# TSAL_3_5_16.net
KiCad netlist of a schematic drawn in EAGLE
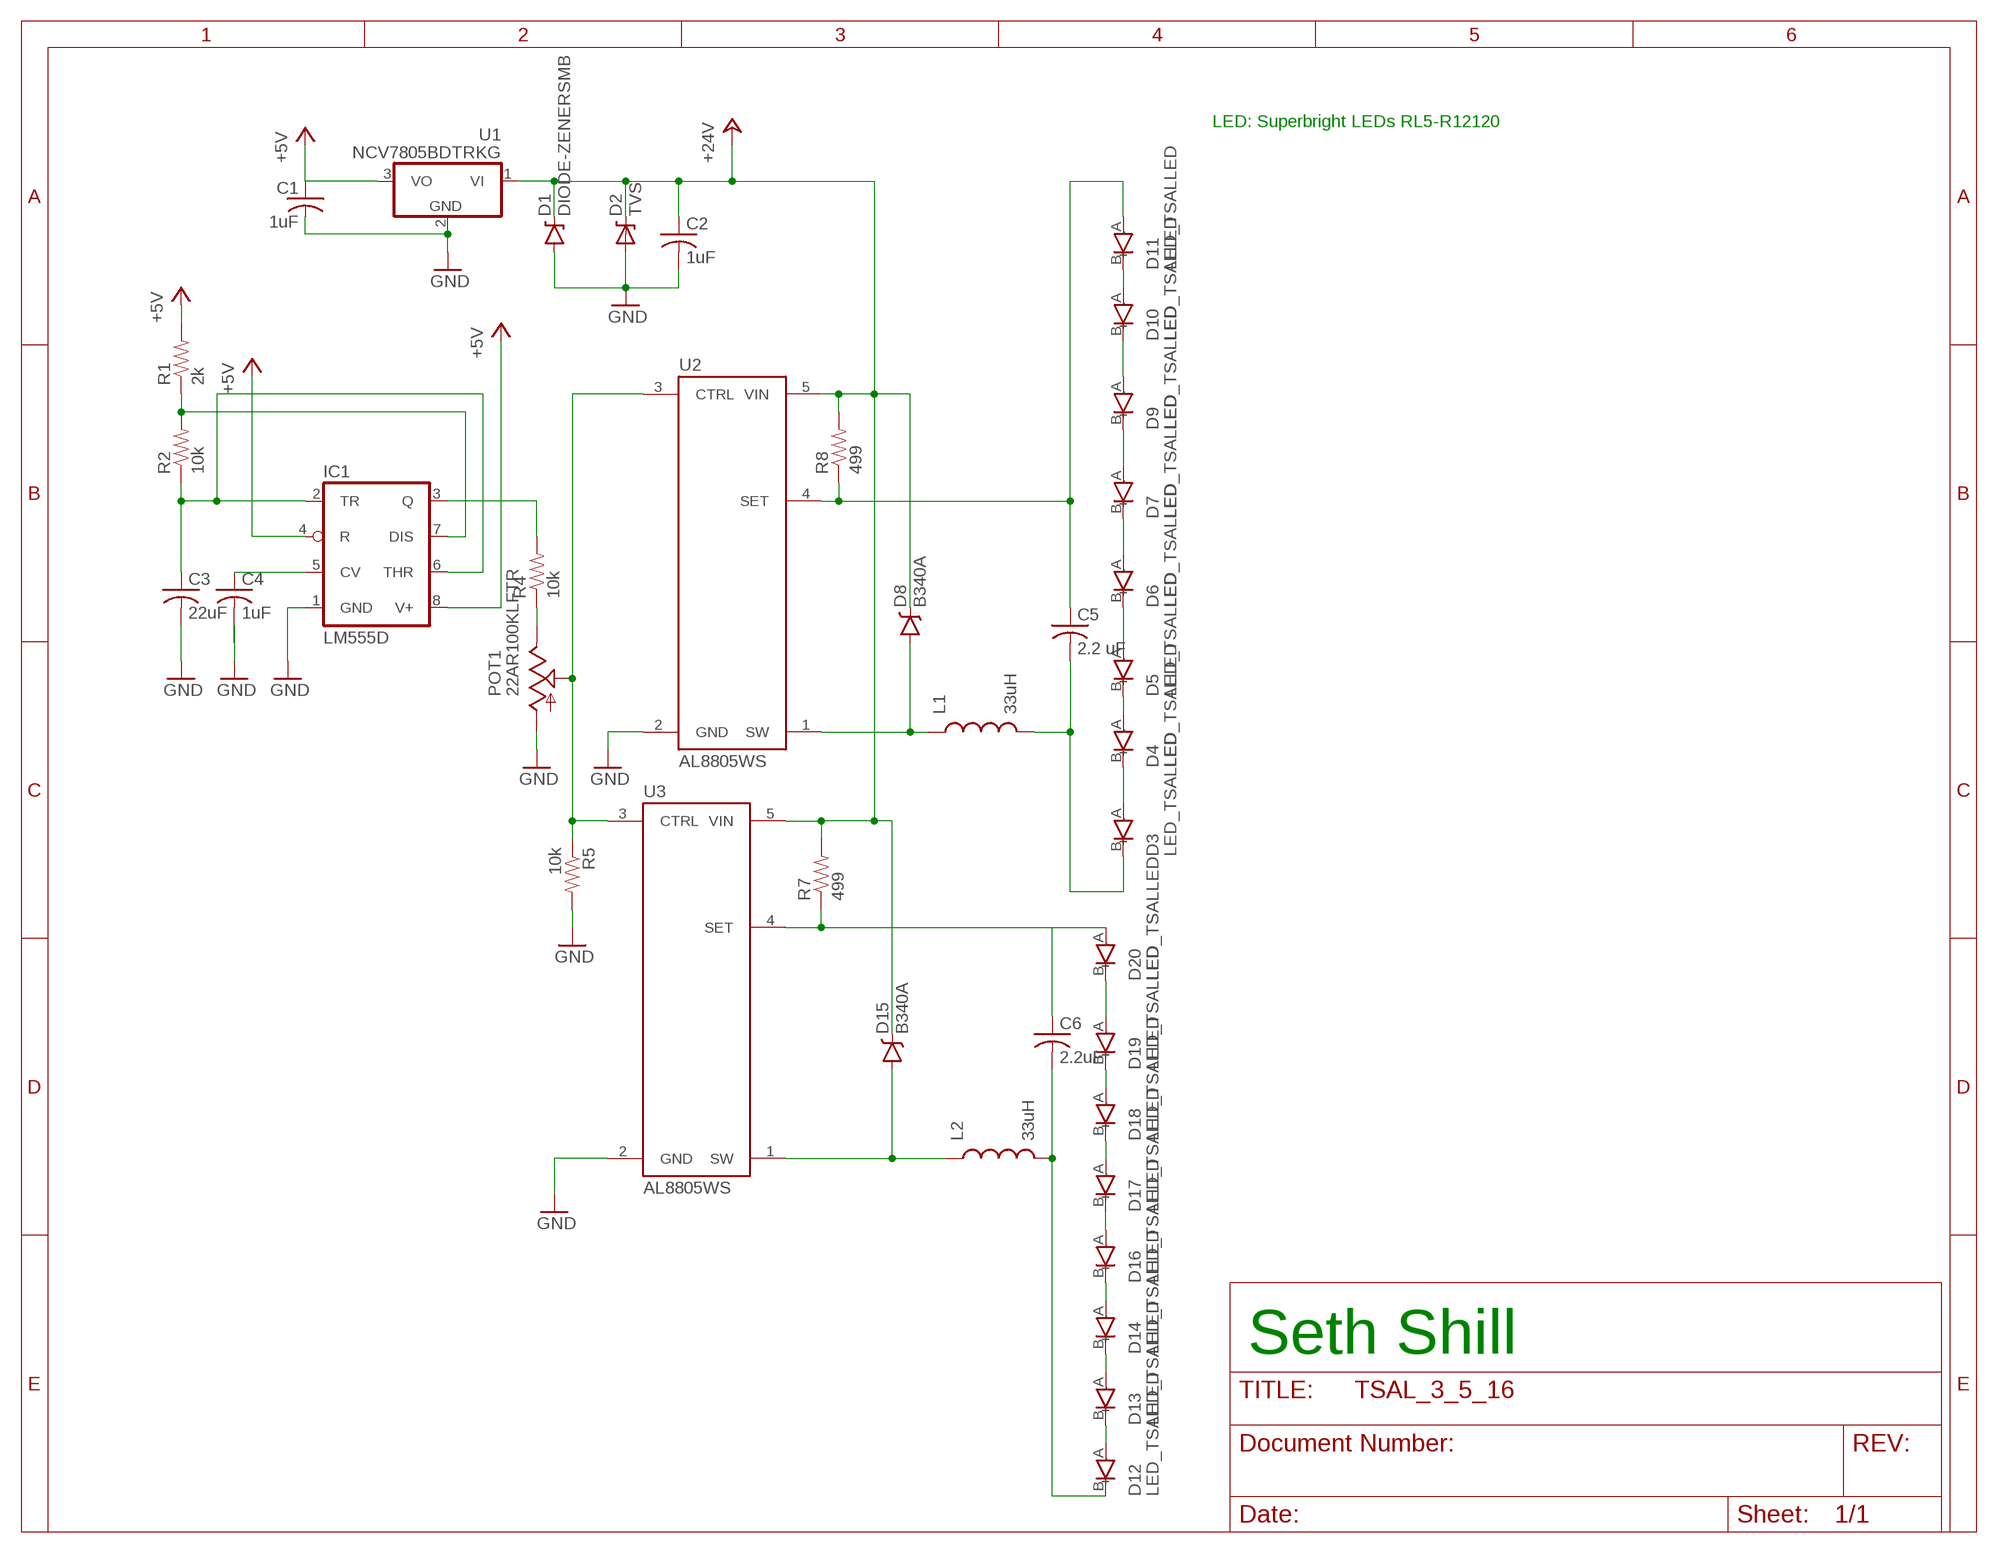
[diagram p0: schematic, sheet 1]

(export (version "E")
  (design (tool "Eeschema 10.0.6"))
  (components
    (comp (ref "C1")
      (value "1uF")
      (footprint "eagle-import:0805@1")
      (fields (field (name "PARTNO") "UMK212F105ZG-T"))
      (libsource (lib "eagle-import") (part "CAP_1UF_50V_0805"))
    )
    (comp (ref "C2")
      (value "1uF")
      (footprint "eagle-import:0805@1")
      (fields (field (name "PARTNO") "UMK212F105ZG-T"))
      (libsource (lib "eagle-import") (part "CAP_1UF_50V_0805"))
    )
    (comp (ref "C3")
      (value "22uF")
      (footprint "eagle-import:0805@1")
      (fields (field (name "PARTNO") "CL21A226MQCLQNC"))
      (libsource (lib "eagle-import") (part "CAP_22UF_6.3V_0805"))
    )
    (comp (ref "C4")
      (value "1uF")
      (footprint "eagle-import:0805@1")
      (fields (field (name "PARTNO") "UMK212F105ZG-T"))
      (libsource (lib "eagle-import") (part "CAP_1UF_50V_0805"))
    )
    (comp (ref "C5")
      (value "2.2 uF")
      (footprint "eagle-import:0603@1")
      (fields (field (name "PARTNO") "EMK107F225ZA-T"))
      (libsource (lib "eagle-import") (part "CAP_2.2UF_16V_0603"))
    )
    (comp (ref "C6")
      (value "2.2uF")
      (footprint "eagle-import:0603@1")
      (fields (field (name "PARTNO") "EMK107F225ZA-T"))
      (libsource (lib "eagle-import") (part "CAP_2.2UF_16V_0603"))
    )
    (comp (ref "D1")
      (value "DIODE-ZENERSMB")
      (footprint "eagle-import:SMB-DIODE")
      (libsource (lib "eagle-import") (part "DIODE-ZENERSMB"))
    )
    (comp (ref "D2")
      (value "TVS")
      (footprint "eagle-import:DO-214AC")
      (libsource (lib "eagle-import") (part "TVS"))
    )
    (comp (ref "D3")
      (value "LED_TSALLED")
      (footprint "eagle-import:LED_TSAL")
      (libsource (lib "eagle-import") (part "LED_TSALLED"))
    )
    (comp (ref "D4")
      (value "LED_TSALLED")
      (footprint "eagle-import:LED_TSAL")
      (libsource (lib "eagle-import") (part "LED_TSALLED"))
    )
    (comp (ref "D5")
      (value "LED_TSALLED")
      (footprint "eagle-import:LED_TSAL")
      (libsource (lib "eagle-import") (part "LED_TSALLED"))
    )
    (comp (ref "D6")
      (value "LED_TSALLED")
      (footprint "eagle-import:LED_TSAL")
      (libsource (lib "eagle-import") (part "LED_TSALLED"))
    )
    (comp (ref "D7")
      (value "LED_TSALLED")
      (footprint "eagle-import:LED_TSAL")
      (libsource (lib "eagle-import") (part "LED_TSALLED"))
    )
    (comp (ref "D8")
      (value "B340A")
      (footprint "eagle-import:SMA-DIODE")
      (libsource (lib "eagle-import") (part "DIODE-SCHOTTKY-B340A"))
    )
    (comp (ref "D9")
      (value "LED_TSALLED")
      (footprint "eagle-import:LED_TSAL")
      (libsource (lib "eagle-import") (part "LED_TSALLED"))
    )
    (comp (ref "D10")
      (value "LED_TSALLED")
      (footprint "eagle-import:LED_TSAL")
      (libsource (lib "eagle-import") (part "LED_TSALLED"))
    )
    (comp (ref "D11")
      (value "LED_TSALLED")
      (footprint "eagle-import:LED_TSAL")
      (libsource (lib "eagle-import") (part "LED_TSALLED"))
    )
    (comp (ref "D12")
      (value "LED_TSALLED")
      (footprint "eagle-import:LED_TSAL")
      (libsource (lib "eagle-import") (part "LED_TSALLED"))
    )
    (comp (ref "D13")
      (value "LED_TSALLED")
      (footprint "eagle-import:LED_TSAL")
      (libsource (lib "eagle-import") (part "LED_TSALLED"))
    )
    (comp (ref "D14")
      (value "LED_TSALLED")
      (footprint "eagle-import:LED_TSAL")
      (libsource (lib "eagle-import") (part "LED_TSALLED"))
    )
    (comp (ref "D15")
      (value "B340A")
      (footprint "eagle-import:SMA-DIODE")
      (libsource (lib "eagle-import") (part "DIODE-SCHOTTKY-B340A"))
    )
    (comp (ref "D16")
      (value "LED_TSALLED")
      (footprint "eagle-import:LED_TSAL")
      (libsource (lib "eagle-import") (part "LED_TSALLED"))
    )
    (comp (ref "D17")
      (value "LED_TSALLED")
      (footprint "eagle-import:LED_TSAL")
      (libsource (lib "eagle-import") (part "LED_TSALLED"))
    )
    (comp (ref "D18")
      (value "LED_TSALLED")
      (footprint "eagle-import:LED_TSAL")
      (libsource (lib "eagle-import") (part "LED_TSALLED"))
    )
    (comp (ref "D19")
      (value "LED_TSALLED")
      (footprint "eagle-import:LED_TSAL")
      (libsource (lib "eagle-import") (part "LED_TSALLED"))
    )
    (comp (ref "D20")
      (value "LED_TSALLED")
      (footprint "eagle-import:LED_TSAL")
      (libsource (lib "eagle-import") (part "LED_TSALLED"))
    )
    (comp (ref "IC1")
      (value "LM555D")
      (footprint "eagle-import:SO08")
      (libsource (lib "eagle-import") (part "555DLM"))
    )
    (comp (ref "L1")
      (value "33uH")
      (footprint "eagle-import:1007")
      (fields (field (name "PARTNO") "CB2518T330K"))
      (libsource (lib "eagle-import") (part "INDUCTOR1007"))
    )
    (comp (ref "L2")
      (value "33uH")
      (footprint "eagle-import:1007")
      (fields (field (name "PARTNO") "CB2518T330K"))
      (libsource (lib "eagle-import") (part "INDUCTOR1007"))
    )
    (comp (ref "POT1")
      (value "22AR100KLFTR")
      (footprint "eagle-import:22AR100KLFTR")
      (libsource (lib "eagle-import") (part "22AR100KLFTR"))
    )
    (comp (ref "R1")
      (value "2k")
      (footprint "eagle-import:0805@1")
      (fields (field (name "PARTNO") "RC0805FR-072KL"))
      (libsource (lib "eagle-import") (part "RES_2K_1%_0805"))
    )
    (comp (ref "R2")
      (value "10k")
      (footprint "eagle-import:0805@1")
      (fields (field (name "PARTNO") "RC0805FR-0710KL"))
      (libsource (lib "eagle-import") (part "RES_10K_1%_0805"))
    )
    (comp (ref "R4")
      (value "10k")
      (footprint "eagle-import:0805@1")
      (fields (field (name "PARTNO") "RC0805FR-0710KL"))
      (libsource (lib "eagle-import") (part "RES_10K_1%_0805"))
    )
    (comp (ref "R5")
      (value "10k")
      (footprint "eagle-import:0805@1")
      (fields (field (name "PARTNO") "RC0805FR-0710KL"))
      (libsource (lib "eagle-import") (part "RES_10K_1%_0805"))
    )
    (comp (ref "R7")
      (value "499")
      (footprint "eagle-import:0603@1")
      (fields (field (name "PARTNO") "RC0603FR-07499RL"))
      (libsource (lib "eagle-import") (part "RES_499_1%"))
    )
    (comp (ref "R8")
      (value "499")
      (footprint "eagle-import:0603@1")
      (fields (field (name "PARTNO") "RC0603FR-07499RL"))
      (libsource (lib "eagle-import") (part "RES_499_1%"))
    )
    (comp (ref "U1")
      (value "NCV7805BDTRKG")
      (footprint "eagle-import:DPAK")
      (libsource (lib "eagle-import") (part "NCV7805BDTRKG"))
    )
    (comp (ref "U2")
      (value "AL8805WS")
      (footprint "eagle-import:SOT23-5")
      (libsource (lib "eagle-import") (part "AL8805"))
    )
    (comp (ref "U3")
      (value "AL8805WS")
      (footprint "eagle-import:SOT23-5")
      (libsource (lib "eagle-import") (part "AL8805"))
    )
  )
  (nets
    (net (code "1") (name "+5V") (class "Default")
      (node (ref "C1") (pin "1") (pinfunction "+_1") (pintype "passive"))
      (node (ref "IC1") (pin "4") (pinfunction "R_4") (pintype "input"))
      (node (ref "IC1") (pin "8") (pinfunction "V+_8") (pintype "power_in"))
      (node (ref "R1") (pin "2") (pinfunction "2_2") (pintype "passive"))
      (node (ref "U1") (pin "3") (pinfunction "VO_3") (pintype "passive"))
    )
    (net (code "2") (name "+24V") (class "Default")
      (node (ref "C2") (pin "1") (pinfunction "+_1") (pintype "passive"))
      (node (ref "D1") (pin "C") (pinfunction "C_C") (pintype "passive"))
      (node (ref "D15") (pin "C") (pinfunction "C_C") (pintype "passive"))
      (node (ref "D2") (pin "C") (pinfunction "C_C") (pintype "passive"))
      (node (ref "D8") (pin "C") (pinfunction "C_C") (pintype "passive"))
      (node (ref "R7") (pin "2") (pinfunction "2_2") (pintype "passive"))
      (node (ref "R8") (pin "2") (pinfunction "2_2") (pintype "passive"))
      (node (ref "U1") (pin "1") (pinfunction "VI_1") (pintype "input"))
      (node (ref "U2") (pin "5") (pinfunction "VIN_5") (pintype "bidirectional"))
      (node (ref "U3") (pin "5") (pinfunction "VIN_5") (pintype "bidirectional"))
    )
    (net (code "3") (name "GND") (class "Default")
      (node (ref "C1") (pin "2") (pinfunction "-_2") (pintype "passive"))
      (node (ref "C2") (pin "2") (pinfunction "-_2") (pintype "passive"))
      (node (ref "C3") (pin "2") (pinfunction "-_2") (pintype "passive"))
      (node (ref "C4") (pin "2") (pinfunction "-_2") (pintype "passive"))
      (node (ref "D1") (pin "A") (pinfunction "A_A") (pintype "passive"))
      (node (ref "D2") (pin "A") (pinfunction "A_A") (pintype "passive"))
      (node (ref "IC1") (pin "1") (pinfunction "GND_1") (pintype "power_in"))
      (node (ref "POT1") (pin "3") (pinfunction "CW_3") (pintype "passive"))
      (node (ref "R5") (pin "2") (pinfunction "2_2") (pintype "passive"))
      (node (ref "U1") (pin "2") (pinfunction "GND_2") (pintype "passive"))
      (node (ref "U2") (pin "2") (pinfunction "GND_2") (pintype "bidirectional"))
      (node (ref "U3") (pin "2") (pinfunction "GND_2") (pintype "bidirectional"))
    )
    (net (code "4") (name "Net-(C3-+)") (class "Default")
      (node (ref "C3") (pin "1") (pinfunction "+_1") (pintype "passive"))
      (node (ref "IC1") (pin "2") (pinfunction "TR_2") (pintype "input"))
      (node (ref "IC1") (pin "6") (pinfunction "THR_6") (pintype "input"))
      (node (ref "R2") (pin "1") (pinfunction "1_1") (pintype "passive"))
    )
    (net (code "5") (name "Net-(C4-+)") (class "Default")
      (node (ref "C4") (pin "1") (pinfunction "+_1") (pintype "passive"))
      (node (ref "IC1") (pin "5") (pinfunction "CV_5") (pintype "input"))
    )
    (net (code "6") (name "Net-(C5-+)") (class "Default")
      (node (ref "C5") (pin "1") (pinfunction "+_1") (pintype "passive"))
      (node (ref "D11") (pin "A") (pinfunction "+_A") (pintype "bidirectional"))
      (node (ref "R8") (pin "1") (pinfunction "1_1") (pintype "passive"))
      (node (ref "U2") (pin "4") (pinfunction "SET_4") (pintype "bidirectional"))
    )
    (net (code "7") (name "Net-(C5--)") (class "Default")
      (node (ref "C5") (pin "2") (pinfunction "-_2") (pintype "passive"))
      (node (ref "D3") (pin "B") (pinfunction "-_B") (pintype "bidirectional"))
      (node (ref "L1") (pin "2") (pinfunction "2_2") (pintype "passive"))
    )
    (net (code "8") (name "Net-(C6-+)") (class "Default")
      (node (ref "C6") (pin "1") (pinfunction "+_1") (pintype "passive"))
      (node (ref "D20") (pin "A") (pinfunction "+_A") (pintype "bidirectional"))
      (node (ref "R7") (pin "1") (pinfunction "1_1") (pintype "passive"))
      (node (ref "U3") (pin "4") (pinfunction "SET_4") (pintype "bidirectional"))
    )
    (net (code "9") (name "Net-(C6--)") (class "Default")
      (node (ref "C6") (pin "2") (pinfunction "-_2") (pintype "passive"))
      (node (ref "D12") (pin "B") (pinfunction "-_B") (pintype "bidirectional"))
      (node (ref "L2") (pin "2") (pinfunction "2_2") (pintype "passive"))
    )
    (net (code "10") (name "Net-(D3-+)") (class "Default")
      (node (ref "D3") (pin "A") (pinfunction "+_A") (pintype "bidirectional"))
      (node (ref "D4") (pin "B") (pinfunction "-_B") (pintype "bidirectional"))
    )
    (net (code "11") (name "Net-(D4-+)") (class "Default")
      (node (ref "D4") (pin "A") (pinfunction "+_A") (pintype "bidirectional"))
      (node (ref "D5") (pin "B") (pinfunction "-_B") (pintype "bidirectional"))
    )
    (net (code "12") (name "Net-(D5-+)") (class "Default")
      (node (ref "D5") (pin "A") (pinfunction "+_A") (pintype "bidirectional"))
      (node (ref "D6") (pin "B") (pinfunction "-_B") (pintype "bidirectional"))
    )
    (net (code "13") (name "Net-(D6-+)") (class "Default")
      (node (ref "D6") (pin "A") (pinfunction "+_A") (pintype "bidirectional"))
      (node (ref "D7") (pin "B") (pinfunction "-_B") (pintype "bidirectional"))
    )
    (net (code "14") (name "Net-(D7-+)") (class "Default")
      (node (ref "D7") (pin "A") (pinfunction "+_A") (pintype "bidirectional"))
      (node (ref "D9") (pin "B") (pinfunction "-_B") (pintype "bidirectional"))
    )
    (net (code "15") (name "Net-(D10-+)") (class "Default")
      (node (ref "D10") (pin "A") (pinfunction "+_A") (pintype "bidirectional"))
      (node (ref "D11") (pin "B") (pinfunction "-_B") (pintype "bidirectional"))
    )
    (net (code "16") (name "Net-(D10--)") (class "Default")
      (node (ref "D10") (pin "B") (pinfunction "-_B") (pintype "bidirectional"))
      (node (ref "D9") (pin "A") (pinfunction "+_A") (pintype "bidirectional"))
    )
    (net (code "17") (name "Net-(D12-+)") (class "Default")
      (node (ref "D12") (pin "A") (pinfunction "+_A") (pintype "bidirectional"))
      (node (ref "D13") (pin "B") (pinfunction "-_B") (pintype "bidirectional"))
    )
    (net (code "18") (name "Net-(D13-+)") (class "Default")
      (node (ref "D13") (pin "A") (pinfunction "+_A") (pintype "bidirectional"))
      (node (ref "D14") (pin "B") (pinfunction "-_B") (pintype "bidirectional"))
    )
    (net (code "19") (name "Net-(D14-+)") (class "Default")
      (node (ref "D14") (pin "A") (pinfunction "+_A") (pintype "bidirectional"))
      (node (ref "D16") (pin "B") (pinfunction "-_B") (pintype "bidirectional"))
    )
    (net (code "20") (name "Net-(D16-+)") (class "Default")
      (node (ref "D16") (pin "A") (pinfunction "+_A") (pintype "bidirectional"))
      (node (ref "D17") (pin "B") (pinfunction "-_B") (pintype "bidirectional"))
    )
    (net (code "21") (name "Net-(D17-+)") (class "Default")
      (node (ref "D17") (pin "A") (pinfunction "+_A") (pintype "bidirectional"))
      (node (ref "D18") (pin "B") (pinfunction "-_B") (pintype "bidirectional"))
    )
    (net (code "22") (name "Net-(D18-+)") (class "Default")
      (node (ref "D18") (pin "A") (pinfunction "+_A") (pintype "bidirectional"))
      (node (ref "D19") (pin "B") (pinfunction "-_B") (pintype "bidirectional"))
    )
    (net (code "23") (name "Net-(D19-+)") (class "Default")
      (node (ref "D19") (pin "A") (pinfunction "+_A") (pintype "bidirectional"))
      (node (ref "D20") (pin "B") (pinfunction "-_B") (pintype "bidirectional"))
    )
    (net (code "24") (name "Net-(IC1-DIS)") (class "Default")
      (node (ref "IC1") (pin "7") (pinfunction "DIS_7") (pintype "input"))
      (node (ref "R1") (pin "1") (pinfunction "1_1") (pintype "passive"))
      (node (ref "R2") (pin "2") (pinfunction "2_2") (pintype "passive"))
    )
    (net (code "25") (name "Net-(IC1-Q)") (class "Default")
      (node (ref "IC1") (pin "3") (pinfunction "Q_3") (pintype "output"))
      (node (ref "R4") (pin "2") (pinfunction "2_2") (pintype "passive"))
    )
    (net (code "26") (name "Net-(POT1-CCW)") (class "Default")
      (node (ref "POT1") (pin "1") (pinfunction "CCW_1") (pintype "passive"))
      (node (ref "R4") (pin "1") (pinfunction "1_1") (pintype "passive"))
    )
    (net (code "27") (name "Net-(POT1-W)") (class "Default")
      (node (ref "POT1") (pin "2") (pinfunction "W_2") (pintype "passive"))
      (node (ref "R5") (pin "1") (pinfunction "1_1") (pintype "passive"))
      (node (ref "U2") (pin "3") (pinfunction "CTRL_3") (pintype "bidirectional"))
      (node (ref "U3") (pin "3") (pinfunction "CTRL_3") (pintype "bidirectional"))
    )
    (net (code "28") (name "Net-(U2-SW)") (class "Default")
      (node (ref "D8") (pin "A") (pinfunction "A_A") (pintype "passive"))
      (node (ref "L1") (pin "1") (pinfunction "1_1") (pintype "passive"))
      (node (ref "U2") (pin "1") (pinfunction "SW_1") (pintype "bidirectional"))
    )
    (net (code "29") (name "Net-(U3-SW)") (class "Default")
      (node (ref "D15") (pin "A") (pinfunction "A_A") (pintype "passive"))
      (node (ref "L2") (pin "1") (pinfunction "1_1") (pintype "passive"))
      (node (ref "U3") (pin "1") (pinfunction "SW_1") (pintype "bidirectional"))
    )
  )
)
